# MCU.net
KiCad netlist of a schematic drawn in Altium Designer
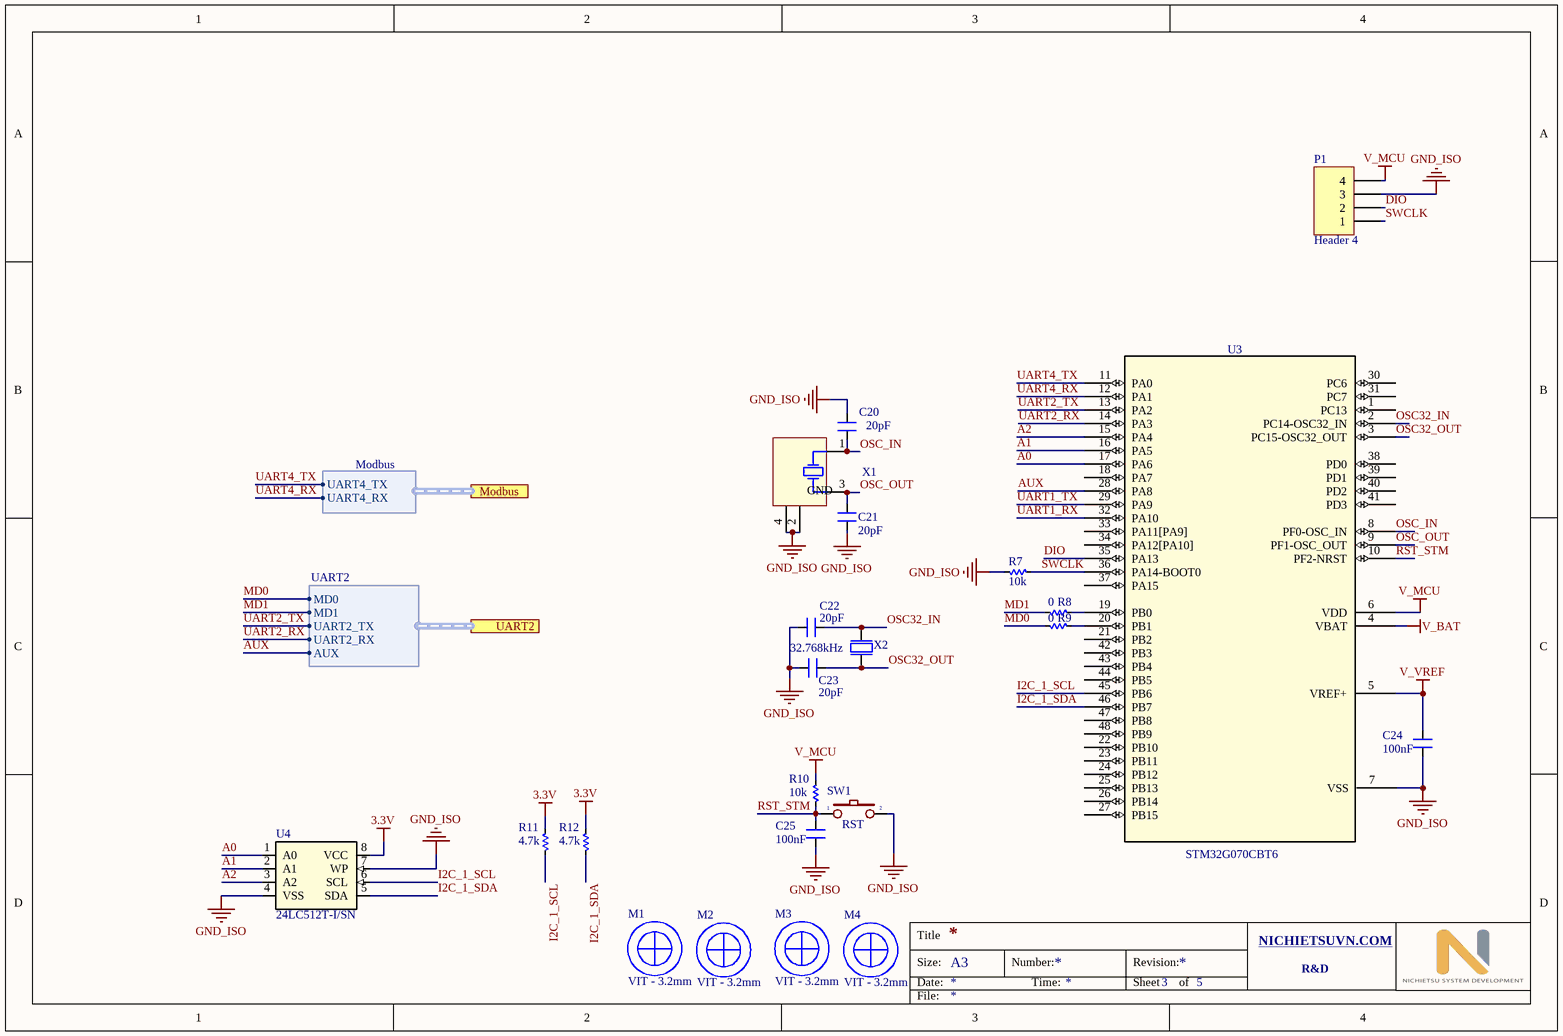
[diagram p0: MCU.SchDoc]

(export (version "E")
  (design (tool "Eeschema 10.0.6"))
  (components
    (comp (ref "C20") (value "20pF") (footprint "CN-SMD-0603") (libsource (lib "thu vien 3d") (part "CN")))
    (comp (ref "C21") (value "20pF") (footprint "CN-SMD-0603") (libsource (lib "thu vien 3d") (part "CN")))
    (comp (ref "C22") (value "20pF") (footprint "CN-SMD-0603") (libsource (lib "thu vien 3d") (part "CN")))
    (comp (ref "C23") (value "20pF") (footprint "CN-SMD-0603") (libsource (lib "thu vien 3d") (part "CN")))
    (comp (ref "C24") (value "100nF") (footprint "CN-SMD-0603") (libsource (lib "thu vien 3d") (part "CN")))
    (comp (ref "C25") (value "100nF") (footprint "CN-SMD-0603") (libsource (lib "thu vien 3d") (part "CN")))
    (comp (ref "M1")
      (value "VIT - 3.2mm")
      (footprint "VIT - 3.2MM_2")
      (libsource (lib "All Library") (part "VIT - 3.2mm_1"))
    )
    (comp (ref "M2")
      (value "VIT - 3.2mm")
      (footprint "VIT - 3.2MM_2")
      (libsource (lib "All Library") (part "VIT - 3.2mm_1"))
    )
    (comp (ref "M3")
      (value "VIT - 3.2mm")
      (footprint "VIT - 3.2MM_2")
      (libsource (lib "All Library") (part "VIT - 3.2mm_1"))
    )
    (comp (ref "M4")
      (value "VIT - 3.2mm")
      (footprint "VIT - 3.2MM_2")
      (libsource (lib "All Library") (part "VIT - 3.2mm_1"))
    )
    (comp (ref "P1")
      (value "Header 4")
      (footprint "Header 4")
      (description "Header, 4-Pin")
      (fields (field (name "PUBLISHER") "Altium Limited"))
      (libsource (lib "hphonglib") (part "Header 4"))
    )
    (comp (ref "R7")
      (value "10k")
      (footprint "RES-SMD-0603")
      (description "Resistor")
      (fields
        (field (name "MANUFACTURER") "Generic Components")
        (field (name "PUBLISHER") "Altium Hobart Technology Centre")
      )
      (libsource (lib "thu vien 3d") (part "Res-SMD"))
    )
    (comp (ref "R8")
      (value "0")
      (footprint "RES-SMD-0603")
      (description "Resistor")
      (fields
        (field (name "MANUFACTURER") "Generic Components")
        (field (name "PUBLISHER") "Altium Hobart Technology Centre")
      )
      (libsource (lib "thu vien 3d") (part "Res-SMD"))
    )
    (comp (ref "R9")
      (value "0")
      (footprint "RES-SMD-0603")
      (description "Resistor")
      (fields
        (field (name "MANUFACTURER") "Generic Components")
        (field (name "PUBLISHER") "Altium Hobart Technology Centre")
      )
      (libsource (lib "thu vien 3d") (part "Res-SMD"))
    )
    (comp (ref "R10")
      (value "10k")
      (footprint "RES-SMD-0603")
      (description "Resistor")
      (fields
        (field (name "MANUFACTURER") "Generic Components")
        (field (name "PUBLISHER") "Altium Hobart Technology Centre")
      )
      (libsource (lib "thu vien 3d") (part "Res-SMD"))
    )
    (comp (ref "R11")
      (value "4.7k")
      (footprint "RES-SMD-0603")
      (description "Resistor")
      (fields
        (field (name "MANUFACTURER") "Generic Components")
        (field (name "PUBLISHER") "Altium Hobart Technology Centre")
      )
      (libsource (lib "thu vien 3d") (part "Res-SMD"))
    )
    (comp (ref "R12")
      (value "4.7k")
      (footprint "RES-SMD-0603")
      (description "Resistor")
      (fields
        (field (name "MANUFACTURER") "Generic Components")
        (field (name "PUBLISHER") "Altium Hobart Technology Centre")
      )
      (libsource (lib "thu vien 3d") (part "Res-SMD"))
    )
    (comp (ref "SW1")
      (value "RST")
      (footprint "SW1-SMD")
      (description "Switch button 2 pin")
      (libsource (lib "thu vien 3d") (part "SW2"))
    )
    (comp (ref "U3")
      (value "STM32G070CBT6")
      (footprint "STM32G070CBT6")
      (description "No Description Available")
      (fields (field (name "COPYRIGHT") "Copyright (C) 2018 Accelerated Designs. All rights reserved"))
      (libsource (lib "Nichietsuvn") (part "STM32G070CBT6"))
    )
    (comp (ref "U4")
      (value "24LC512T-I/SN")
      (footprint "24LC512")
      (description "No Description Available")
      (fields (field (name "COPYRIGHT") "Copyright (C) 2022 Ultra Librarian. All rights reserved."))
      (libsource (lib "All Library") (part "24LC512T-I/SN"))
    )
    (comp (ref "X1")
      (value "XT4")
      (footprint "XT4-16.000MHz-4_V")
      (description "Crystal, 16 MHz, -30 to 85 degC, 3.2 x 2.5 x 0.9 mm SMD")
      (libsource (lib "thu vien 3d") (part "XT4"))
    )
    (comp (ref "X2")
      (value "32.768kHz")
      (footprint "XTAL_3215")
      (description "XTAL SMD 3215, 32.768kHz, Cl=9pF, Total Tol: ±50ppm")
      (fields
        (field (name "PART NUMBER") "XTAL_SMD3215_32.768kHz_9pF_General")
        (field (name "PUBLISHER") "Nordic Semiconductor")
      )
      (libsource (lib "Nichietsuvn") (part "XTAL_SMD3215"))
    )
  )
  (nets
    (net (code "3") (name "/A0") (class "Default")
      (node (ref "U3") (pin "17") (pinfunction "PA6_17") (pintype "bidirectional"))
      (node (ref "U4") (pin "1") (pinfunction "A0_1") (pintype "passive"))
    )
    (net (code "4") (name "/A1") (class "Default")
      (node (ref "U3") (pin "16") (pinfunction "PA5_16") (pintype "bidirectional"))
      (node (ref "U4") (pin "2") (pinfunction "A1_2") (pintype "passive"))
    )
    (net (code "5") (name "/A2") (class "Default")
      (node (ref "U3") (pin "15") (pinfunction "PA4_15") (pintype "bidirectional"))
      (node (ref "U4") (pin "3") (pinfunction "A2_3") (pintype "passive"))
    )
    (net (code "6") (name "/AUX") (class "Default")
      (node (ref "U3") (pin "28") (pinfunction "PA8_28") (pintype "bidirectional"))
    )
    (net (code "7") (name "/DIO") (class "Default")
      (node (ref "P1") (pin "2") (pinfunction "2_2") (pintype "passive"))
      (node (ref "U3") (pin "35") (pinfunction "PA13_35") (pintype "bidirectional"))
    )
    (net (code "8") (name "/I2C_1_SCL") (class "Default")
      (node (ref "R11") (pin "2") (pinfunction "2_2") (pintype "passive"))
      (node (ref "U3") (pin "45") (pinfunction "PB6_45") (pintype "bidirectional"))
      (node (ref "U4") (pin "6") (pinfunction "SCL_6") (pintype "input"))
    )
    (net (code "9") (name "/I2C_1_SDA") (class "Default")
      (node (ref "R12") (pin "2") (pinfunction "2_2") (pintype "passive"))
      (node (ref "U3") (pin "46") (pinfunction "PB7_46") (pintype "bidirectional"))
      (node (ref "U4") (pin "5") (pinfunction "SDA_5") (pintype "bidirectional"))
    )
    (net (code "10") (name "/MD0") (class "Default")
      (node (ref "R9") (pin "2") (pinfunction "2_2") (pintype "passive"))
    )
    (net (code "11") (name "/MD1") (class "Default")
      (node (ref "R8") (pin "2") (pinfunction "2_2") (pintype "passive"))
    )
    (net (code "12") (name "/OSC32_IN") (class "Default")
      (node (ref "C22") (pin "2") (pinfunction "2_2") (pintype "passive"))
      (node (ref "U3") (pin "2") (pinfunction "PC14-OSC32_IN_2") (pintype "bidirectional"))
      (node (ref "X2") (pin "2") (pinfunction "out_2") (pintype "passive"))
    )
    (net (code "13") (name "/OSC32_OUT") (class "Default")
      (node (ref "C23") (pin "2") (pinfunction "2_2") (pintype "passive"))
      (node (ref "U3") (pin "3") (pinfunction "PC15-OSC32_OUT_3") (pintype "bidirectional"))
      (node (ref "X2") (pin "1") (pinfunction "inp_1") (pintype "passive"))
    )
    (net (code "14") (name "/OSC_IN") (class "Default")
      (node (ref "C20") (pin "1") (pinfunction "1_1") (pintype "passive"))
      (node (ref "U3") (pin "8") (pinfunction "PF0-OSC_IN_8") (pintype "bidirectional"))
      (node (ref "X1") (pin "1") (pinfunction "XTAL_1") (pintype "passive"))
    )
    (net (code "15") (name "/OSC_OUT") (class "Default")
      (node (ref "C21") (pin "2") (pinfunction "2_2") (pintype "passive"))
      (node (ref "U3") (pin "9") (pinfunction "PF1-OSC_OUT_9") (pintype "bidirectional"))
      (node (ref "X1") (pin "3") (pinfunction "XTAL_3") (pintype "passive"))
    )
    (net (code "16") (name "/RST_STM") (class "Default")
      (node (ref "C25") (pin "1") (pinfunction "1_1") (pintype "passive"))
      (node (ref "R10") (pin "2") (pinfunction "2_2") (pintype "passive"))
      (node (ref "SW1") (pin "1") (pinfunction "1_1") (pintype "passive"))
      (node (ref "U3") (pin "10") (pinfunction "PF2-NRST_10") (pintype "bidirectional"))
    )
    (net (code "17") (name "/SWCLK") (class "Default")
      (node (ref "P1") (pin "1") (pinfunction "1_1") (pintype "passive"))
      (node (ref "R7") (pin "1") (pinfunction "1_1") (pintype "passive"))
      (node (ref "U3") (pin "36") (pinfunction "PA14-BOOT0_36") (pintype "bidirectional"))
    )
    (net (code "18") (name "/UART1_RX") (class "Default")
      (node (ref "U3") (pin "32") (pinfunction "PA10_32") (pintype "bidirectional"))
    )
    (net (code "19") (name "/UART1_TX") (class "Default")
      (node (ref "U3") (pin "29") (pinfunction "PA9_29") (pintype "bidirectional"))
    )
    (net (code "20") (name "/UART2_RX") (class "Default")
      (node (ref "U3") (pin "14") (pinfunction "PA3_14") (pintype "bidirectional"))
    )
    (net (code "21") (name "/UART2_TX") (class "Default")
      (node (ref "U3") (pin "13") (pinfunction "PA2_13") (pintype "bidirectional"))
    )
    (net (code "22") (name "/UART4_RX") (class "Default")
      (node (ref "U3") (pin "12") (pinfunction "PA1_12") (pintype "bidirectional"))
    )
    (net (code "23") (name "/UART4_TX") (class "Default")
      (node (ref "U3") (pin "11") (pinfunction "PA0_11") (pintype "bidirectional"))
    )
    (net (code "26") (name "3.3V") (class "Default")
      (node (ref "R11") (pin "1") (pinfunction "1_1") (pintype "passive"))
      (node (ref "R12") (pin "1") (pinfunction "1_1") (pintype "passive"))
      (node (ref "U4") (pin "8") (pinfunction "VCC_8") (pintype "power_in"))
    )
    (net (code "27") (name "GND_ISO") (class "Default")
      (node (ref "C20") (pin "2") (pinfunction "2_2") (pintype "passive"))
      (node (ref "C21") (pin "1") (pinfunction "1_1") (pintype "passive"))
      (node (ref "C22") (pin "1") (pinfunction "1_1") (pintype "passive"))
      (node (ref "C23") (pin "1") (pinfunction "1_1") (pintype "passive"))
      (node (ref "C24") (pin "2") (pinfunction "2_2") (pintype "passive"))
      (node (ref "C25") (pin "2") (pinfunction "2_2") (pintype "passive"))
      (node (ref "P1") (pin "3") (pinfunction "3_3") (pintype "passive"))
      (node (ref "R7") (pin "2") (pinfunction "2_2") (pintype "passive"))
      (node (ref "SW1") (pin "2") (pinfunction "2_2") (pintype "passive"))
      (node (ref "U3") (pin "7") (pinfunction "VSS_7") (pintype "power_in"))
      (node (ref "U4") (pin "4") (pinfunction "VSS_4") (pintype "power_in"))
      (node (ref "U4") (pin "7") (pinfunction "WP_7") (pintype "input"))
      (node (ref "X1") (pin "2") (pinfunction "GND_2") (pintype "power_in"))
      (node (ref "X1") (pin "4") (pinfunction "GND_4") (pintype "power_in"))
    )
    (net (code "28") (name "Net-(U3-PB0)") (class "Default")
      (node (ref "R8") (pin "1") (pinfunction "1_1") (pintype "passive"))
      (node (ref "U3") (pin "19") (pinfunction "PB0_19") (pintype "bidirectional"))
    )
    (net (code "29") (name "Net-(U3-PB1)") (class "Default")
      (node (ref "R9") (pin "1") (pinfunction "1_1") (pintype "passive"))
      (node (ref "U3") (pin "20") (pinfunction "PB1_20") (pintype "bidirectional"))
    )
    (net (code "30") (name "V_BAT") (class "Default")
      (node (ref "U3") (pin "4") (pinfunction "VBAT_4") (pintype "power_in"))
    )
    (net (code "31") (name "V_MCU") (class "Default")
      (node (ref "P1") (pin "4") (pinfunction "4_4") (pintype "passive"))
      (node (ref "R10") (pin "1") (pinfunction "1_1") (pintype "passive"))
      (node (ref "U3") (pin "6") (pinfunction "VDD_6") (pintype "power_in"))
    )
    (net (code "32") (name "V_VREF") (class "Default")
      (node (ref "C24") (pin "1") (pinfunction "1_1") (pintype "passive"))
      (node (ref "U3") (pin "5") (pinfunction "VREF+_5") (pintype "power_in"))
    )
    (net (code "33") (name "unconnected-(U3-PA7-Pad18)") (class "Default")
      (node (ref "U3") (pin "18") (pinfunction "PA7_18") (pintype "bidirectional"))
    )
    (net (code "34") (name "unconnected-(U3-PA11[PA9]-Pad33)") (class "Default")
      (node (ref "U3") (pin "33") (pinfunction "PA11[PA9]_33") (pintype "bidirectional"))
    )
    (net (code "35") (name "unconnected-(U3-PA12[PA10]-Pad34)") (class "Default")
      (node (ref "U3") (pin "34") (pinfunction "PA12[PA10]_34") (pintype "bidirectional"))
    )
    (net (code "36") (name "unconnected-(U3-PA15-Pad37)") (class "Default")
      (node (ref "U3") (pin "37") (pinfunction "PA15_37") (pintype "bidirectional"))
    )
    (net (code "37") (name "unconnected-(U3-PB2-Pad21)") (class "Default")
      (node (ref "U3") (pin "21") (pinfunction "PB2_21") (pintype "bidirectional"))
    )
    (net (code "38") (name "unconnected-(U3-PB3-Pad42)") (class "Default")
      (node (ref "U3") (pin "42") (pinfunction "PB3_42") (pintype "bidirectional"))
    )
    (net (code "39") (name "unconnected-(U3-PB4-Pad43)") (class "Default")
      (node (ref "U3") (pin "43") (pinfunction "PB4_43") (pintype "bidirectional"))
    )
    (net (code "40") (name "unconnected-(U3-PB5-Pad44)") (class "Default")
      (node (ref "U3") (pin "44") (pinfunction "PB5_44") (pintype "bidirectional"))
    )
    (net (code "41") (name "unconnected-(U3-PB8-Pad47)") (class "Default")
      (node (ref "U3") (pin "47") (pinfunction "PB8_47") (pintype "bidirectional"))
    )
    (net (code "42") (name "unconnected-(U3-PB9-Pad48)") (class "Default")
      (node (ref "U3") (pin "48") (pinfunction "PB9_48") (pintype "bidirectional"))
    )
    (net (code "43") (name "unconnected-(U3-PB10-Pad22)") (class "Default")
      (node (ref "U3") (pin "22") (pinfunction "PB10_22") (pintype "bidirectional"))
    )
    (net (code "44") (name "unconnected-(U3-PB11-Pad23)") (class "Default")
      (node (ref "U3") (pin "23") (pinfunction "PB11_23") (pintype "bidirectional"))
    )
    (net (code "45") (name "unconnected-(U3-PB12-Pad24)") (class "Default")
      (node (ref "U3") (pin "24") (pinfunction "PB12_24") (pintype "bidirectional"))
    )
    (net (code "46") (name "unconnected-(U3-PB13-Pad25)") (class "Default")
      (node (ref "U3") (pin "25") (pinfunction "PB13_25") (pintype "bidirectional"))
    )
    (net (code "47") (name "unconnected-(U3-PB14-Pad26)") (class "Default")
      (node (ref "U3") (pin "26") (pinfunction "PB14_26") (pintype "bidirectional"))
    )
    (net (code "48") (name "unconnected-(U3-PB15-Pad27)") (class "Default")
      (node (ref "U3") (pin "27") (pinfunction "PB15_27") (pintype "bidirectional"))
    )
    (net (code "49") (name "unconnected-(U3-PC6-Pad30)") (class "Default")
      (node (ref "U3") (pin "30") (pinfunction "PC6_30") (pintype "bidirectional"))
    )
    (net (code "50") (name "unconnected-(U3-PC7-Pad31)") (class "Default")
      (node (ref "U3") (pin "31") (pinfunction "PC7_31") (pintype "bidirectional"))
    )
    (net (code "51") (name "unconnected-(U3-PC13-Pad1)") (class "Default")
      (node (ref "U3") (pin "1") (pinfunction "PC13_1") (pintype "bidirectional"))
    )
    (net (code "52") (name "unconnected-(U3-PD0-Pad38)") (class "Default")
      (node (ref "U3") (pin "38") (pinfunction "PD0_38") (pintype "bidirectional"))
    )
    (net (code "53") (name "unconnected-(U3-PD1-Pad39)") (class "Default")
      (node (ref "U3") (pin "39") (pinfunction "PD1_39") (pintype "bidirectional"))
    )
    (net (code "54") (name "unconnected-(U3-PD2-Pad40)") (class "Default")
      (node (ref "U3") (pin "40") (pinfunction "PD2_40") (pintype "bidirectional"))
    )
    (net (code "55") (name "unconnected-(U3-PD3-Pad41)") (class "Default")
      (node (ref "U3") (pin "41") (pinfunction "PD3_41") (pintype "bidirectional"))
    )
  )
)
